# ControllerV3_0_1.net
KiCad netlist of a schematic drawn in Altium Designer
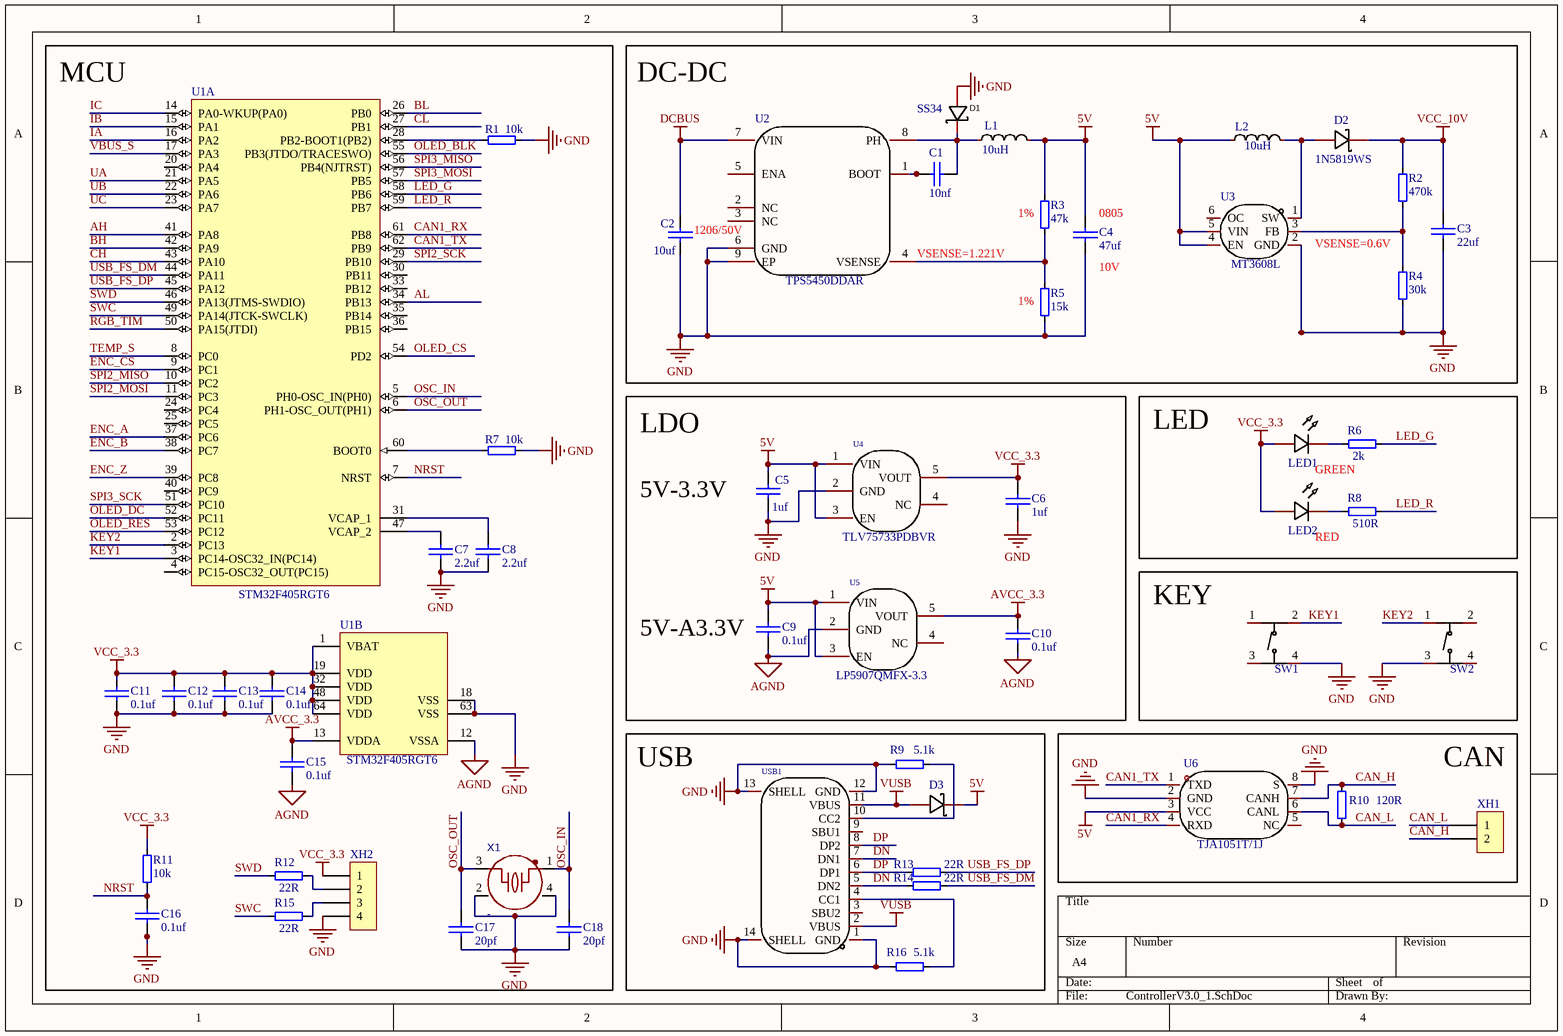
[diagram p0: ControllerV3.0_1.SchDoc]

(export (version "E")
  (design (tool "Eeschema 10.0.6"))
  (components
    (comp (ref "C1")
      (value "10nf")
      (footprint "C0603_S")
      (description "贴片电容")
      (libsource (lib "Controller") (part "CAP"))
    )
    (comp (ref "C2")
      (value "10uf")
      (footprint "C1206_S")
      (description "贴片电容")
      (libsource (lib "Controller") (part "CAP"))
    )
    (comp (ref "C3")
      (value "22uf")
      (footprint "C0603_S")
      (description "贴片电容")
      (libsource (lib "Controller") (part "CAP"))
    )
    (comp (ref "C4")
      (value "47uf")
      (footprint "C0805_S")
      (description "贴片电容")
      (libsource (lib "Controller") (part "CAP"))
    )
    (comp (ref "C5")
      (value "1uf")
      (footprint "C0603_S")
      (description "贴片电容")
      (libsource (lib "Controller") (part "CAP"))
    )
    (comp (ref "C6")
      (value "1uf")
      (footprint "C0603_S")
      (description "贴片电容")
      (libsource (lib "Controller") (part "CAP"))
    )
    (comp (ref "C7")
      (value "2.2uf")
      (footprint "C0603_S")
      (description "贴片电容")
      (libsource (lib "Controller") (part "CAP"))
    )
    (comp (ref "C8")
      (value "2.2uf")
      (footprint "C0603_S")
      (description "贴片电容")
      (libsource (lib "Controller") (part "CAP"))
    )
    (comp (ref "C9")
      (value "0.1uf")
      (footprint "C0603_S")
      (description "贴片电容")
      (libsource (lib "Controller") (part "CAP"))
    )
    (comp (ref "C10")
      (value "0.1uf")
      (footprint "C0603_S")
      (description "贴片电容")
      (libsource (lib "Controller") (part "CAP"))
    )
    (comp (ref "C11")
      (value "0.1uf")
      (footprint "C0603_S")
      (description "贴片电容")
      (libsource (lib "Controller") (part "CAP"))
    )
    (comp (ref "C12")
      (value "0.1uf")
      (footprint "C0603_S")
      (description "贴片电容")
      (libsource (lib "Controller") (part "CAP"))
    )
    (comp (ref "C13")
      (value "0.1uf")
      (footprint "C0603_S")
      (description "贴片电容")
      (libsource (lib "Controller") (part "CAP"))
    )
    (comp (ref "C14")
      (value "0.1uf")
      (footprint "C0603_S")
      (description "贴片电容")
      (libsource (lib "Controller") (part "CAP"))
    )
    (comp (ref "C15")
      (value "0.1uf")
      (footprint "C0603_S")
      (description "贴片电容")
      (libsource (lib "Controller") (part "CAP"))
    )
    (comp (ref "C16")
      (value "0.1uf")
      (footprint "C0603_S")
      (description "贴片电容")
      (libsource (lib "Controller") (part "CAP"))
    )
    (comp (ref "C17")
      (value "20pf")
      (footprint "C0603_S")
      (description "贴片电容")
      (libsource (lib "Controller") (part "CAP"))
    )
    (comp (ref "C18")
      (value "20pf")
      (footprint "C0603_S")
      (description "贴片电容")
      (libsource (lib "Controller") (part "CAP"))
    )
    (comp (ref "D1")
      (value "SS34")
      (footprint "SS34")
      (description "肖特基二极管")
      (fields (field (name "MANUFACTURER") "MDD"))
      (libsource (lib "Controller") (part "SS34"))
    )
    (comp (ref "D2")
      (value "1N5819WS")
      (footprint "SOD-323")
      (description "肖特基二极管")
      (fields (field (name "MANUFACTURER") "Hottech(合科泰)"))
      (libsource (lib "Controller") (part "1N5819WS"))
    )
    (comp (ref "D3")
      (value "1N5819WS")
      (footprint "SOD-323")
      (description "肖特基二极管")
      (fields (field (name "MANUFACTURER") "Hottech(合科泰)"))
      (libsource (lib "Controller") (part "1N5819WS"))
    )
    (comp (ref "L1")
      (value "10uH")
      (footprint "SMD-0420")
      (description "功率电感")
      (libsource (lib "Controller") (part "IND"))
    )
    (comp (ref "L2")
      (value "10uH")
      (footprint "IND-SMD_L3.0-W3.0_SWPA3010S")
      (description "电感值:10uH;精度:±20%;额定电流:920mA;")
      (fields (field (name "MANUFACTURER") "SXN(顺翔诺)") (field (name "MANUFACTURER PART") "SMDRI74-220M"))
      (libsource (lib "Controller") (part "SWPA3015S100MT"))
    )
    (comp (ref "LED1")
      (value "LED_0603-B")
      (footprint "LED_0603")
      (libsource (lib "Controller") (part "LED"))
    )
    (comp (ref "LED2")
      (value "LED_0603-B")
      (footprint "LED_0603")
      (libsource (lib "Controller") (part "LED"))
    )
    (comp (ref "R1")
      (value "10k")
      (footprint "R0603_S")
      (description "贴片电阻")
      (libsource (lib "Controller") (part "RES"))
    )
    (comp (ref "R2")
      (value "470k")
      (footprint "R0603_S")
      (description "贴片电阻")
      (libsource (lib "Controller") (part "RES"))
    )
    (comp (ref "R3")
      (value "47k")
      (footprint "R0603_S")
      (description "贴片电阻")
      (libsource (lib "Controller") (part "RES"))
    )
    (comp (ref "R4")
      (value "30k")
      (footprint "R0603_S")
      (description "贴片电阻")
      (libsource (lib "Controller") (part "RES"))
    )
    (comp (ref "R5")
      (value "15k")
      (footprint "R0603_S")
      (description "贴片电阻")
      (libsource (lib "Controller") (part "RES"))
    )
    (comp (ref "R6")
      (value "2k")
      (footprint "R0603_S")
      (description "贴片电阻")
      (libsource (lib "Controller") (part "RES"))
    )
    (comp (ref "R7")
      (value "10k")
      (footprint "R0603_S")
      (description "贴片电阻")
      (libsource (lib "Controller") (part "RES"))
    )
    (comp (ref "R8")
      (value "510R")
      (footprint "R0603_S")
      (description "贴片电阻")
      (libsource (lib "Controller") (part "RES"))
    )
    (comp (ref "R9")
      (value "5.1k")
      (footprint "R0603_S")
      (description "贴片电阻")
      (libsource (lib "Controller") (part "RES"))
    )
    (comp (ref "R10")
      (value "120R")
      (footprint "R0603_S")
      (description "贴片电阻")
      (libsource (lib "Controller") (part "RES"))
    )
    (comp (ref "R11")
      (value "10k")
      (footprint "R0603_S")
      (description "贴片电阻")
      (libsource (lib "Controller") (part "RES"))
    )
    (comp (ref "R12")
      (value "22R")
      (footprint "R0603_S")
      (description "贴片电阻")
      (libsource (lib "Controller") (part "RES"))
    )
    (comp (ref "R13")
      (value "22R")
      (footprint "R0603_S")
      (description "贴片电阻")
      (libsource (lib "Controller") (part "RES"))
    )
    (comp (ref "R14")
      (value "22R")
      (footprint "R0603_S")
      (description "贴片电阻")
      (libsource (lib "Controller") (part "RES"))
    )
    (comp (ref "R15")
      (value "22R")
      (footprint "R0603_S")
      (description "贴片电阻")
      (libsource (lib "Controller") (part "RES"))
    )
    (comp (ref "R16")
      (value "5.1k")
      (footprint "R0603_S")
      (description "贴片电阻")
      (libsource (lib "Controller") (part "RES"))
    )
    (comp (ref "SW1")
      (value "TS-1187A-B-A-B")
      (footprint "TSW SMD-4*4*1.5")
      (description "轻触开关")
      (fields (field (name "MANUFACTURER") "XKB Connectivity(中国星坤)"))
      (libsource (lib "Controller") (part "TS-1187A-B-A-B"))
    )
    (comp (ref "SW2")
      (value "TS-1187A-B-A-B")
      (footprint "TSW SMD-4*4*1.5")
      (description "轻触开关")
      (fields (field (name "MANUFACTURER") "XKB Connectivity(中国星坤)"))
      (libsource (lib "Controller") (part "TS-1187A-B-A-B"))
    )
    (comp (ref "U1")
      (value "STM32F405RGT6")
      (footprint "LQFP_64")
      (fields (field (name "MANUFACTURER") "STMicroelectronics"))
      (libsource (lib "Controller") (part "STM32F405RGT6"))
    )
    (comp (ref "U2")
      (value "TPS5450DDAR")
      (footprint "SOP-8-EP")
      (fields (field (name "MANUFACTURER") "TI(德州仪器)"))
      (libsource (lib "Controller") (part "TPS5450DDAR"))
    )
    (comp (ref "U3")
      (value "MT3608L")
      (footprint "SOT-23-6")
      (fields (field (name "MANUFACTURER") "西安航天民芯"))
      (libsource (lib "Controller") (part "MT3608L"))
    )
    (comp (ref "U4")
      (value "TLV75733PDBVR")
      (footprint "SOT-23-5")
      (fields (field (name "MANUFACTURER") "RICHTEK(立锜)") (field (name "MANUFACTURER PART") "RT9013-33GB"))
      (libsource (lib "Controller") (part "TLV75733PDBVR"))
    )
    (comp (ref "U5")
      (value "LP5907QMFX-3.3")
      (footprint "SOT-23-5")
      (fields (field (name "MANUFACTURER") "RICHTEK(立锜)") (field (name "MANUFACTURER PART") "RT9013-33GB"))
      (libsource (lib "Controller") (part "LP5907QMFX-3.3"))
    )
    (comp (ref "U6")
      (value "TJA1051T/1J")
      (footprint "SOP-8")
      (description "类型:收发器;数据速率:5Mbps;")
      (fields (field (name "MANUFACTURER") "NXP(恩智浦)"))
      (libsource (lib "Controller") (part "TJA1051T/1J"))
    )
    (comp (ref "USB1")
      (value "TYPE-C 16PIN 2MD(073)")
      (footprint "USB-C-SMD_TYPE-C-6PIN-2MD-073")
      (description "连接器类型:Type-C;标准:-;公母:母座;触点数量:16;端口数量:1;安装方式:卧贴;额定电流 - 电源:5A;工作温度范围:-25℃~+85℃;")
      (fields (field (name "MANUFACTURER") "SHOU HAN(首韩)"))
      (libsource (lib "Controller") (part "TYPE-C 16PIN 2MD(073)"))
    )
    (comp (ref "X1")
      (value "-")
      (footprint "OSC 3225-4P")
      (description "8MHz")
      (fields
        (field (name "BOM_SUPPLIER PART") "C843260")
        (field (name "BOM_MANUFACTURER PART") "NX2016SA-32MHZ-STD-CZS-5")
        (field (name "CONTRIBUTOR") "LCSC")
      )
      (libsource (lib "Controller") (part "四脚无源晶振"))
    )
    (comp (ref "XH1")
      (value "XH2.54-WS-2P")
      (footprint "XH2.54-WS-2P")
      (libsource (lib "Controller") (part "XH2.54-WS-2P"))
    )
    (comp (ref "XH2")
      (value "GH1.25-WS-4P")
      (footprint "GH1.25-WS-4P")
      (libsource (lib "Controller") (part "GH1.25-WS-4P"))
    )
  )
  (nets
    (net (code "1") (name "/AH") (class "Default")
      (node (ref "U1") (pin "41") (pinfunction "PA8_41") (pintype "bidirectional"))
    )
    (net (code "2") (name "/AL") (class "Default")
      (node (ref "U1") (pin "34") (pinfunction "PB13_34") (pintype "bidirectional"))
    )
    (net (code "3") (name "/BH") (class "Default")
      (node (ref "U1") (pin "42") (pinfunction "PA9_42") (pintype "bidirectional"))
    )
    (net (code "4") (name "/BL") (class "Default")
      (node (ref "U1") (pin "26") (pinfunction "PB0_26") (pintype "bidirectional"))
    )
    (net (code "5") (name "/CAN1_RX") (class "Default")
      (node (ref "U1") (pin "61") (pinfunction "PB8_61") (pintype "bidirectional"))
      (node (ref "U6") (pin "4") (pinfunction "RXD_4") (pintype "passive"))
    )
    (net (code "6") (name "/CAN1_TX") (class "Default")
      (node (ref "U1") (pin "62") (pinfunction "PB9_62") (pintype "bidirectional"))
      (node (ref "U6") (pin "1") (pinfunction "TXD_1") (pintype "passive"))
    )
    (net (code "7") (name "/CAN_H") (class "Default")
      (node (ref "R10") (pin "2") (pinfunction "2_2") (pintype "passive"))
      (node (ref "U6") (pin "7") (pinfunction "CANH_7") (pintype "passive"))
      (node (ref "XH1") (pin "2") (pinfunction "2_2") (pintype "passive"))
    )
    (net (code "8") (name "/CAN_L") (class "Default")
      (node (ref "R10") (pin "1") (pinfunction "1_1") (pintype "passive"))
      (node (ref "U6") (pin "6") (pinfunction "CANL_6") (pintype "passive"))
      (node (ref "XH1") (pin "1") (pinfunction "1_1") (pintype "passive"))
    )
    (net (code "9") (name "/CH") (class "Default")
      (node (ref "U1") (pin "43") (pinfunction "PA10_43") (pintype "bidirectional"))
    )
    (net (code "10") (name "/CL") (class "Default")
      (node (ref "U1") (pin "27") (pinfunction "PB1_27") (pintype "bidirectional"))
    )
    (net (code "11") (name "/DN") (class "Default")
      (node (ref "R14") (pin "1") (pinfunction "1_1") (pintype "passive"))
      (node (ref "USB1") (pin "5") (pinfunction "DN2_5") (pintype "passive"))
      (node (ref "USB1") (pin "7") (pinfunction "DN1_7") (pintype "passive"))
    )
    (net (code "12") (name "/DP") (class "Default")
      (node (ref "R13") (pin "1") (pinfunction "1_1") (pintype "passive"))
      (node (ref "USB1") (pin "6") (pinfunction "DP1_6") (pintype "passive"))
      (node (ref "USB1") (pin "8") (pinfunction "DP2_8") (pintype "passive"))
    )
    (net (code "13") (name "/ENC_A") (class "Default")
      (node (ref "U1") (pin "37") (pinfunction "PC6_37") (pintype "bidirectional"))
    )
    (net (code "14") (name "/ENC_B") (class "Default")
      (node (ref "U1") (pin "38") (pinfunction "PC7_38") (pintype "bidirectional"))
    )
    (net (code "15") (name "/ENC_CS") (class "Default")
      (node (ref "U1") (pin "9") (pinfunction "PC1_9") (pintype "bidirectional"))
    )
    (net (code "16") (name "/ENC_Z") (class "Default")
      (node (ref "U1") (pin "39") (pinfunction "PC8_39") (pintype "bidirectional"))
    )
    (net (code "17") (name "/IA") (class "Default")
      (node (ref "U1") (pin "16") (pinfunction "PA2_16") (pintype "bidirectional"))
    )
    (net (code "18") (name "/IB") (class "Default")
      (node (ref "U1") (pin "15") (pinfunction "PA1_15") (pintype "bidirectional"))
    )
    (net (code "19") (name "/IC") (class "Default")
      (node (ref "U1") (pin "14") (pinfunction "PA0-WKUP(PA0)_14") (pintype "bidirectional"))
    )
    (net (code "20") (name "/KEY1") (class "Default")
      (node (ref "SW1") (pin "2") (pinfunction "B_2") (pintype "passive"))
      (node (ref "U1") (pin "3") (pinfunction "PC14-OSC32_IN(PC14)_3") (pintype "bidirectional"))
    )
    (net (code "21") (name "/KEY2") (class "Default")
      (node (ref "SW2") (pin "1") (pinfunction "A_1") (pintype "passive"))
      (node (ref "U1") (pin "2") (pinfunction "PC13_2") (pintype "bidirectional"))
    )
    (net (code "22") (name "/LED_G") (class "Default")
      (node (ref "R6") (pin "2") (pinfunction "2_2") (pintype "passive"))
      (node (ref "U1") (pin "58") (pinfunction "PB6_58") (pintype "bidirectional"))
    )
    (net (code "23") (name "/LED_R") (class "Default")
      (node (ref "R8") (pin "2") (pinfunction "2_2") (pintype "passive"))
      (node (ref "U1") (pin "59") (pinfunction "PB7_59") (pintype "bidirectional"))
    )
    (net (code "24") (name "/NRST") (class "Default")
      (node (ref "C16") (pin "2") (pinfunction "2_2") (pintype "passive"))
      (node (ref "R11") (pin "1") (pinfunction "1_1") (pintype "passive"))
      (node (ref "U1") (pin "7") (pinfunction "NRST_7") (pintype "bidirectional"))
    )
    (net (code "25") (name "/OLED_BLK") (class "Default")
      (node (ref "U1") (pin "55") (pinfunction "PB3(JTDO/TRACESWO)_55") (pintype "bidirectional"))
    )
    (net (code "26") (name "/OLED_CS") (class "Default")
      (node (ref "U1") (pin "54") (pinfunction "PD2_54") (pintype "bidirectional"))
    )
    (net (code "27") (name "/OLED_DC") (class "Default")
      (node (ref "U1") (pin "52") (pinfunction "PC11_52") (pintype "bidirectional"))
    )
    (net (code "28") (name "/OLED_RES") (class "Default")
      (node (ref "U1") (pin "53") (pinfunction "PC12_53") (pintype "bidirectional"))
    )
    (net (code "29") (name "/OSC_IN") (class "Default")
      (node (ref "C18") (pin "1") (pinfunction "1_1") (pintype "passive"))
      (node (ref "U1") (pin "5") (pinfunction "PH0-OSC_IN(PH0)_5") (pintype "bidirectional"))
      (node (ref "X1") (pin "1") (pinfunction "1_1") (pintype "passive"))
    )
    (net (code "30") (name "/OSC_OUT") (class "Default")
      (node (ref "C17") (pin "1") (pinfunction "1_1") (pintype "passive"))
      (node (ref "U1") (pin "6") (pinfunction "PH1-OSC_OUT(PH1)_6") (pintype "bidirectional"))
      (node (ref "X1") (pin "3") (pinfunction "3_3") (pintype "passive"))
    )
    (net (code "31") (name "/RGB_TIM") (class "Default")
      (node (ref "U1") (pin "50") (pinfunction "PA15(JTDI)_50") (pintype "bidirectional"))
    )
    (net (code "32") (name "/SPI2_MISO") (class "Default")
      (node (ref "U1") (pin "10") (pinfunction "PC2_10") (pintype "bidirectional"))
    )
    (net (code "33") (name "/SPI2_MOSI") (class "Default")
      (node (ref "U1") (pin "11") (pinfunction "PC3_11") (pintype "bidirectional"))
    )
    (net (code "34") (name "/SPI2_SCK") (class "Default")
      (node (ref "U1") (pin "29") (pinfunction "PB10_29") (pintype "bidirectional"))
    )
    (net (code "35") (name "/SPI3_MISO") (class "Default")
      (node (ref "U1") (pin "56") (pinfunction "PB4(NJTRST)_56") (pintype "bidirectional"))
    )
    (net (code "36") (name "/SPI3_MOSI") (class "Default")
      (node (ref "U1") (pin "57") (pinfunction "PB5_57") (pintype "bidirectional"))
    )
    (net (code "37") (name "/SPI3_SCK") (class "Default")
      (node (ref "U1") (pin "51") (pinfunction "PC10_51") (pintype "bidirectional"))
    )
    (net (code "38") (name "/SWC") (class "Default")
      (node (ref "R15") (pin "1") (pinfunction "1_1") (pintype "passive"))
      (node (ref "U1") (pin "49") (pinfunction "PA14(JTCK-SWCLK)_49") (pintype "bidirectional"))
    )
    (net (code "39") (name "/SWD") (class "Default")
      (node (ref "R12") (pin "1") (pinfunction "1_1") (pintype "passive"))
      (node (ref "U1") (pin "46") (pinfunction "PA13(JTMS-SWDIO)_46") (pintype "bidirectional"))
    )
    (net (code "40") (name "/TEMP_S") (class "Default")
      (node (ref "U1") (pin "8") (pinfunction "PC0_8") (pintype "bidirectional"))
    )
    (net (code "41") (name "/UA") (class "Default")
      (node (ref "U1") (pin "21") (pinfunction "PA5_21") (pintype "bidirectional"))
    )
    (net (code "42") (name "/UB") (class "Default")
      (node (ref "U1") (pin "22") (pinfunction "PA6_22") (pintype "bidirectional"))
    )
    (net (code "43") (name "/UC") (class "Default")
      (node (ref "U1") (pin "23") (pinfunction "PA7_23") (pintype "bidirectional"))
    )
    (net (code "44") (name "/USB_FS_DM") (class "Default")
      (node (ref "R14") (pin "2") (pinfunction "2_2") (pintype "passive"))
      (node (ref "U1") (pin "44") (pinfunction "PA11_44") (pintype "bidirectional"))
    )
    (net (code "45") (name "/USB_FS_DP") (class "Default")
      (node (ref "R13") (pin "2") (pinfunction "2_2") (pintype "passive"))
      (node (ref "U1") (pin "45") (pinfunction "PA12_45") (pintype "bidirectional"))
    )
    (net (code "46") (name "/VBUS_S") (class "Default")
      (node (ref "U1") (pin "17") (pinfunction "PA3_17") (pintype "bidirectional"))
    )
    (net (code "47") (name "5V") (class "Default")
      (node (ref "C4") (pin "1") (pinfunction "1_1") (pintype "passive"))
      (node (ref "C5") (pin "1") (pinfunction "1_1") (pintype "passive"))
      (node (ref "C9") (pin "1") (pinfunction "1_1") (pintype "passive"))
      (node (ref "D3") (pin "1") (pinfunction "K_1") (pintype "passive"))
      (node (ref "L1") (pin "2") (pinfunction "2_2") (pintype "passive"))
      (node (ref "L2") (pin "1") (pinfunction "1_1") (pintype "passive"))
      (node (ref "R3") (pin "2") (pinfunction "2_2") (pintype "passive"))
      (node (ref "U3") (pin "4") (pinfunction "EN_4") (pintype "passive"))
      (node (ref "U3") (pin "5") (pinfunction "VIN_5") (pintype "passive"))
      (node (ref "U4") (pin "1") (pinfunction "VIN_1") (pintype "passive"))
      (node (ref "U4") (pin "3") (pinfunction "EN_3") (pintype "passive"))
      (node (ref "U5") (pin "1") (pinfunction "VIN_1") (pintype "passive"))
      (node (ref "U5") (pin "3") (pinfunction "EN_3") (pintype "passive"))
      (node (ref "U6") (pin "3") (pinfunction "VCC_3") (pintype "passive"))
    )
    (net (code "48") (name "AGND") (class "Default")
      (node (ref "C10") (pin "2") (pinfunction "2_2") (pintype "passive"))
      (node (ref "C15") (pin "2") (pinfunction "2_2") (pintype "passive"))
      (node (ref "C9") (pin "2") (pinfunction "2_2") (pintype "passive"))
      (node (ref "U1") (pin "12") (pinfunction "VSSA_12") (pintype "power_in"))
      (node (ref "U5") (pin "2") (pinfunction "GND_2") (pintype "passive"))
    )
    (net (code "49") (name "AVCC_3.3") (class "Default")
      (node (ref "C10") (pin "1") (pinfunction "1_1") (pintype "passive"))
      (node (ref "C15") (pin "1") (pinfunction "1_1") (pintype "passive"))
      (node (ref "U1") (pin "13") (pinfunction "VDDA_13") (pintype "power_in"))
      (node (ref "U5") (pin "5") (pinfunction "VOUT_5") (pintype "passive"))
    )
    (net (code "50") (name "DCBUS") (class "Default")
      (node (ref "C2") (pin "1") (pinfunction "1_1") (pintype "passive"))
      (node (ref "U2") (pin "7") (pinfunction "VIN_7") (pintype "passive"))
    )
    (net (code "51") (name "GND") (class "Default")
      (node (ref "C11") (pin "2") (pinfunction "2_2") (pintype "passive"))
      (node (ref "C12") (pin "2") (pinfunction "2_2") (pintype "passive"))
      (node (ref "C13") (pin "2") (pinfunction "2_2") (pintype "passive"))
      (node (ref "C14") (pin "2") (pinfunction "2_2") (pintype "passive"))
      (node (ref "C16") (pin "1") (pinfunction "1_1") (pintype "passive"))
      (node (ref "C17") (pin "2") (pinfunction "2_2") (pintype "passive"))
      (node (ref "C18") (pin "2") (pinfunction "2_2") (pintype "passive"))
      (node (ref "C2") (pin "2") (pinfunction "2_2") (pintype "passive"))
      (node (ref "C3") (pin "1") (pinfunction "1_1") (pintype "passive"))
      (node (ref "C4") (pin "2") (pinfunction "2_2") (pintype "passive"))
      (node (ref "C5") (pin "2") (pinfunction "2_2") (pintype "passive"))
      (node (ref "C6") (pin "2") (pinfunction "2_2") (pintype "passive"))
      (node (ref "C7") (pin "2") (pinfunction "2_2") (pintype "passive"))
      (node (ref "C8") (pin "2") (pinfunction "2_2") (pintype "passive"))
      (node (ref "D1") (pin "2") (pinfunction "A_2") (pintype "passive"))
      (node (ref "R1") (pin "2") (pinfunction "2_2") (pintype "passive"))
      (node (ref "R16") (pin "1") (pinfunction "1_1") (pintype "passive"))
      (node (ref "R4") (pin "1") (pinfunction "1_1") (pintype "passive"))
      (node (ref "R5") (pin "1") (pinfunction "1_1") (pintype "passive"))
      (node (ref "R7") (pin "2") (pinfunction "2_2") (pintype "passive"))
      (node (ref "R9") (pin "1") (pinfunction "1_1") (pintype "passive"))
      (node (ref "SW1") (pin "4") (pinfunction "D_4") (pintype "passive"))
      (node (ref "SW2") (pin "3") (pinfunction "C_3") (pintype "passive"))
      (node (ref "U1") (pin "18") (pinfunction "VSS_18") (pintype "power_in"))
      (node (ref "U1") (pin "63") (pinfunction "VSS_63") (pintype "power_in"))
      (node (ref "U2") (pin "6") (pinfunction "GND_6") (pintype "passive"))
      (node (ref "U2") (pin "9") (pinfunction "EP_9") (pintype "passive"))
      (node (ref "U3") (pin "2") (pinfunction "GND_2") (pintype "passive"))
      (node (ref "U4") (pin "2") (pinfunction "GND_2") (pintype "passive"))
      (node (ref "U6") (pin "2") (pinfunction "GND_2") (pintype "passive"))
      (node (ref "U6") (pin "8") (pinfunction "S_8") (pintype "passive"))
      (node (ref "USB1") (pin "1") (pinfunction "GND_1") (pintype "passive"))
      (node (ref "USB1") (pin "12") (pinfunction "GND_12") (pintype "passive"))
      (node (ref "USB1") (pin "13") (pinfunction "SHELL_13") (pintype "passive"))
      (node (ref "USB1") (pin "14") (pinfunction "SHELL_14") (pintype "passive"))
      (node (ref "X1") (pin "2") (pinfunction "GND_2") (pintype "passive"))
      (node (ref "X1") (pin "4") (pinfunction "GND_4") (pintype "passive"))
      (node (ref "XH2") (pin "4") (pinfunction "4_4") (pintype "passive"))
    )
    (net (code "52") (name "Net-(D1-K)") (class "Default")
      (node (ref "C1") (pin "2") (pinfunction "2_2") (pintype "passive"))
      (node (ref "D1") (pin "1") (pinfunction "K_1") (pintype "passive"))
      (node (ref "L1") (pin "1") (pinfunction "1_1") (pintype "passive"))
      (node (ref "U2") (pin "8") (pinfunction "PH_8") (pintype "passive"))
    )
    (net (code "53") (name "Net-(D2-A)") (class "Default")
      (node (ref "D2") (pin "2") (pinfunction "A_2") (pintype "passive"))
      (node (ref "L2") (pin "2") (pinfunction "2_2") (pintype "passive"))
      (node (ref "U3") (pin "1") (pinfunction "SW_1") (pintype "passive"))
    )
    (net (code "54") (name "Net-(LED1-C)") (class "Default")
      (node (ref "LED1") (pin "1") (pinfunction "C_1") (pintype "passive"))
      (node (ref "R6") (pin "1") (pinfunction "1_1") (pintype "passive"))
    )
    (net (code "55") (name "Net-(LED2-C)") (class "Default")
      (node (ref "LED2") (pin "1") (pinfunction "C_1") (pintype "passive"))
      (node (ref "R8") (pin "1") (pinfunction "1_1") (pintype "passive"))
    )
    (net (code "56") (name "Net-(R12-Pad2)") (class "Default")
      (node (ref "R12") (pin "2") (pinfunction "2_2") (pintype "passive"))
      (node (ref "XH2") (pin "2") (pinfunction "2_2") (pintype "passive"))
    )
    (net (code "57") (name "Net-(R15-Pad2)") (class "Default")
      (node (ref "R15") (pin "2") (pinfunction "2_2") (pintype "passive"))
      (node (ref "XH2") (pin "3") (pinfunction "3_3") (pintype "passive"))
    )
    (net (code "58") (name "Net-(U1A-BOOT0)") (class "Default")
      (node (ref "R7") (pin "1") (pinfunction "1_1") (pintype "passive"))
      (node (ref "U1") (pin "60") (pinfunction "BOOT0_60") (pintype "input"))
    )
    (net (code "59") (name "Net-(U1A-PB2-BOOT1(PB2))") (class "Default")
      (node (ref "R1") (pin "1") (pinfunction "1_1") (pintype "passive"))
      (node (ref "U1") (pin "28") (pinfunction "PB2-BOOT1(PB2)_28") (pintype "bidirectional"))
    )
    (net (code "60") (name "Net-(U1A-VCAP_1)") (class "Default")
      (node (ref "C8") (pin "1") (pinfunction "1_1") (pintype "passive"))
      (node (ref "U1") (pin "31") (pinfunction "VCAP_1_31") (pintype "power_in"))
    )
    (net (code "61") (name "Net-(U1A-VCAP_2)") (class "Default")
      (node (ref "C7") (pin "1") (pinfunction "1_1") (pintype "passive"))
      (node (ref "U1") (pin "47") (pinfunction "VCAP_2_47") (pintype "power_in"))
    )
    (net (code "62") (name "Net-(U2-BOOT)") (class "Default")
      (node (ref "C1") (pin "1") (pinfunction "1_1") (pintype "passive"))
      (node (ref "U2") (pin "1") (pinfunction "BOOT_1") (pintype "passive"))
    )
    (net (code "63") (name "Net-(U2-VSENSE)") (class "Default")
      (node (ref "R3") (pin "1") (pinfunction "1_1") (pintype "passive"))
      (node (ref "R5") (pin "2") (pinfunction "2_2") (pintype "passive"))
      (node (ref "U2") (pin "4") (pinfunction "VSENSE_4") (pintype "passive"))
    )
    (net (code "64") (name "Net-(U3-FB)") (class "Default")
      (node (ref "R2") (pin "1") (pinfunction "1_1") (pintype "passive"))
      (node (ref "R4") (pin "2") (pinfunction "2_2") (pintype "passive"))
      (node (ref "U3") (pin "3") (pinfunction "FB_3") (pintype "passive"))
    )
    (net (code "65") (name "Net-(USB1-CC1)") (class "Default")
      (node (ref "R16") (pin "2") (pinfunction "2_2") (pintype "passive"))
      (node (ref "USB1") (pin "4") (pinfunction "CC1_4") (pintype "passive"))
    )
    (net (code "66") (name "Net-(USB1-CC2)") (class "Default")
      (node (ref "R9") (pin "2") (pinfunction "2_2") (pintype "passive"))
      (node (ref "USB1") (pin "10") (pinfunction "CC2_10") (pintype "passive"))
    )
    (net (code "67") (name "VCC_3.3") (class "Default")
      (node (ref "C11") (pin "1") (pinfunction "1_1") (pintype "passive"))
      (node (ref "C12") (pin "1") (pinfunction "1_1") (pintype "passive"))
      (node (ref "C13") (pin "1") (pinfunction "1_1") (pintype "passive"))
      (node (ref "C14") (pin "1") (pinfunction "1_1") (pintype "passive"))
      (node (ref "C6") (pin "1") (pinfunction "1_1") (pintype "passive"))
      (node (ref "LED1") (pin "2") (pinfunction "A_2") (pintype "passive"))
      (node (ref "LED2") (pin "2") (pinfunction "A_2") (pintype "passive"))
      (node (ref "R11") (pin "2") (pinfunction "2_2") (pintype "passive"))
      (node (ref "U1") (pin "1") (pinfunction "VBAT_1") (pintype "power_in"))
      (node (ref "U1") (pin "19") (pinfunction "VDD_19") (pintype "power_in"))
      (node (ref "U1") (pin "32") (pinfunction "VDD_32") (pintype "power_in"))
      (node (ref "U1") (pin "48") (pinfunction "VDD_48") (pintype "power_in"))
      (node (ref "U1") (pin "64") (pinfunction "VDD_64") (pintype "power_in"))
      (node (ref "U4") (pin "5") (pinfunction "VOUT_5") (pintype "passive"))
      (node (ref "XH2") (pin "1") (pinfunction "1_1") (pintype "passive"))
    )
    (net (code "68") (name "VCC_10V") (class "Default")
      (node (ref "C3") (pin "2") (pinfunction "2_2") (pintype "passive"))
      (node (ref "D2") (pin "1") (pinfunction "K_1") (pintype "passive"))
      (node (ref "R2") (pin "2") (pinfunction "2_2") (pintype "passive"))
    )
    (net (code "69") (name "VUSB") (class "Default")
      (node (ref "D3") (pin "2") (pinfunction "A_2") (pintype "passive"))
      (node (ref "USB1") (pin "11") (pinfunction "VBUS_11") (pintype "passive"))
      (node (ref "USB1") (pin "2") (pinfunction "VBUS_2") (pintype "passive"))
    )
    (net (code "70") (name "unconnected-(SW1-A-Pad1)") (class "Default")
      (node (ref "SW1") (pin "1") (pinfunction "A_1") (pintype "passive"))
    )
    (net (code "71") (name "unconnected-(SW1-C-Pad3)") (class "Default")
      (node (ref "SW1") (pin "3") (pinfunction "C_3") (pintype "passive"))
    )
    (net (code "72") (name "unconnected-(SW2-B-Pad2)") (class "Default")
      (node (ref "SW2") (pin "2") (pinfunction "B_2") (pintype "passive"))
    )
    (net (code "73") (name "unconnected-(SW2-D-Pad4)") (class "Default")
      (node (ref "SW2") (pin "4") (pinfunction "D_4") (pintype "passive"))
    )
    (net (code "74") (name "unconnected-(U1A-PA4-Pad20)") (class "Default")
      (node (ref "U1") (pin "20") (pinfunction "PA4_20") (pintype "bidirectional"))
    )
    (net (code "75") (name "unconnected-(U1A-PB11-Pad30)") (class "Default")
      (node (ref "U1") (pin "30") (pinfunction "PB11_30") (pintype "bidirectional"))
    )
    (net (code "76") (name "unconnected-(U1A-PB12-Pad33)") (class "Default")
      (node (ref "U1") (pin "33") (pinfunction "PB12_33") (pintype "bidirectional"))
    )
    (net (code "77") (name "unconnected-(U1A-PB14-Pad35)") (class "Default")
      (node (ref "U1") (pin "35") (pinfunction "PB14_35") (pintype "bidirectional"))
    )
    (net (code "78") (name "unconnected-(U1A-PB15-Pad36)") (class "Default")
      (node (ref "U1") (pin "36") (pinfunction "PB15_36") (pintype "bidirectional"))
    )
    (net (code "79") (name "unconnected-(U1A-PC4-Pad24)") (class "Default")
      (node (ref "U1") (pin "24") (pinfunction "PC4_24") (pintype "bidirectional"))
    )
    (net (code "80") (name "unconnected-(U1A-PC5-Pad25)") (class "Default")
      (node (ref "U1") (pin "25") (pinfunction "PC5_25") (pintype "bidirectional"))
    )
    (net (code "81") (name "unconnected-(U1A-PC9-Pad40)") (class "Default")
      (node (ref "U1") (pin "40") (pinfunction "PC9_40") (pintype "bidirectional"))
    )
    (net (code "82") (name "unconnected-(U1A-PC15-OSC32_OUT(PC15)-Pad4)") (class "Default")
      (node (ref "U1") (pin "4") (pinfunction "PC15-OSC32_OUT(PC15)_4") (pintype "bidirectional"))
    )
    (net (code "83") (name "unconnected-(U2-ENA-Pad5)") (class "Default")
      (node (ref "U2") (pin "5") (pinfunction "ENA_5") (pintype "passive"))
    )
    (net (code "84") (name "unconnected-(U2-NC-Pad2)") (class "Default")
      (node (ref "U2") (pin "2") (pinfunction "NC_2") (pintype "passive"))
    )
    (net (code "85") (name "unconnected-(U2-NC-Pad3)") (class "Default")
      (node (ref "U2") (pin "3") (pinfunction "NC_3") (pintype "passive"))
    )
    (net (code "86") (name "unconnected-(U3-OC-Pad6)") (class "Default")
      (node (ref "U3") (pin "6") (pinfunction "OC_6") (pintype "passive"))
    )
    (net (code "87") (name "unconnected-(U4-NC-Pad4)") (class "Default")
      (node (ref "U4") (pin "4") (pinfunction "NC_4") (pintype "passive"))
    )
    (net (code "88") (name "unconnected-(U5-NC-Pad4)") (class "Default")
      (node (ref "U5") (pin "4") (pinfunction "NC_4") (pintype "passive"))
    )
    (net (code "89") (name "unconnected-(U6-NC-Pad5)") (class "Default")
      (node (ref "U6") (pin "5") (pinfunction "NC_5") (pintype "passive"))
    )
    (net (code "90") (name "unconnected-(USB1-SBU1-Pad9)") (class "Default")
      (node (ref "USB1") (pin "9") (pinfunction "SBU1_9") (pintype "passive"))
    )
    (net (code "91") (name "unconnected-(USB1-SBU2-Pad3)") (class "Default")
      (node (ref "USB1") (pin "3") (pinfunction "SBU2_3") (pintype "passive"))
    )
  )
)
